# Sheet2.net
KiCad netlist of a schematic drawn in Altium Designer
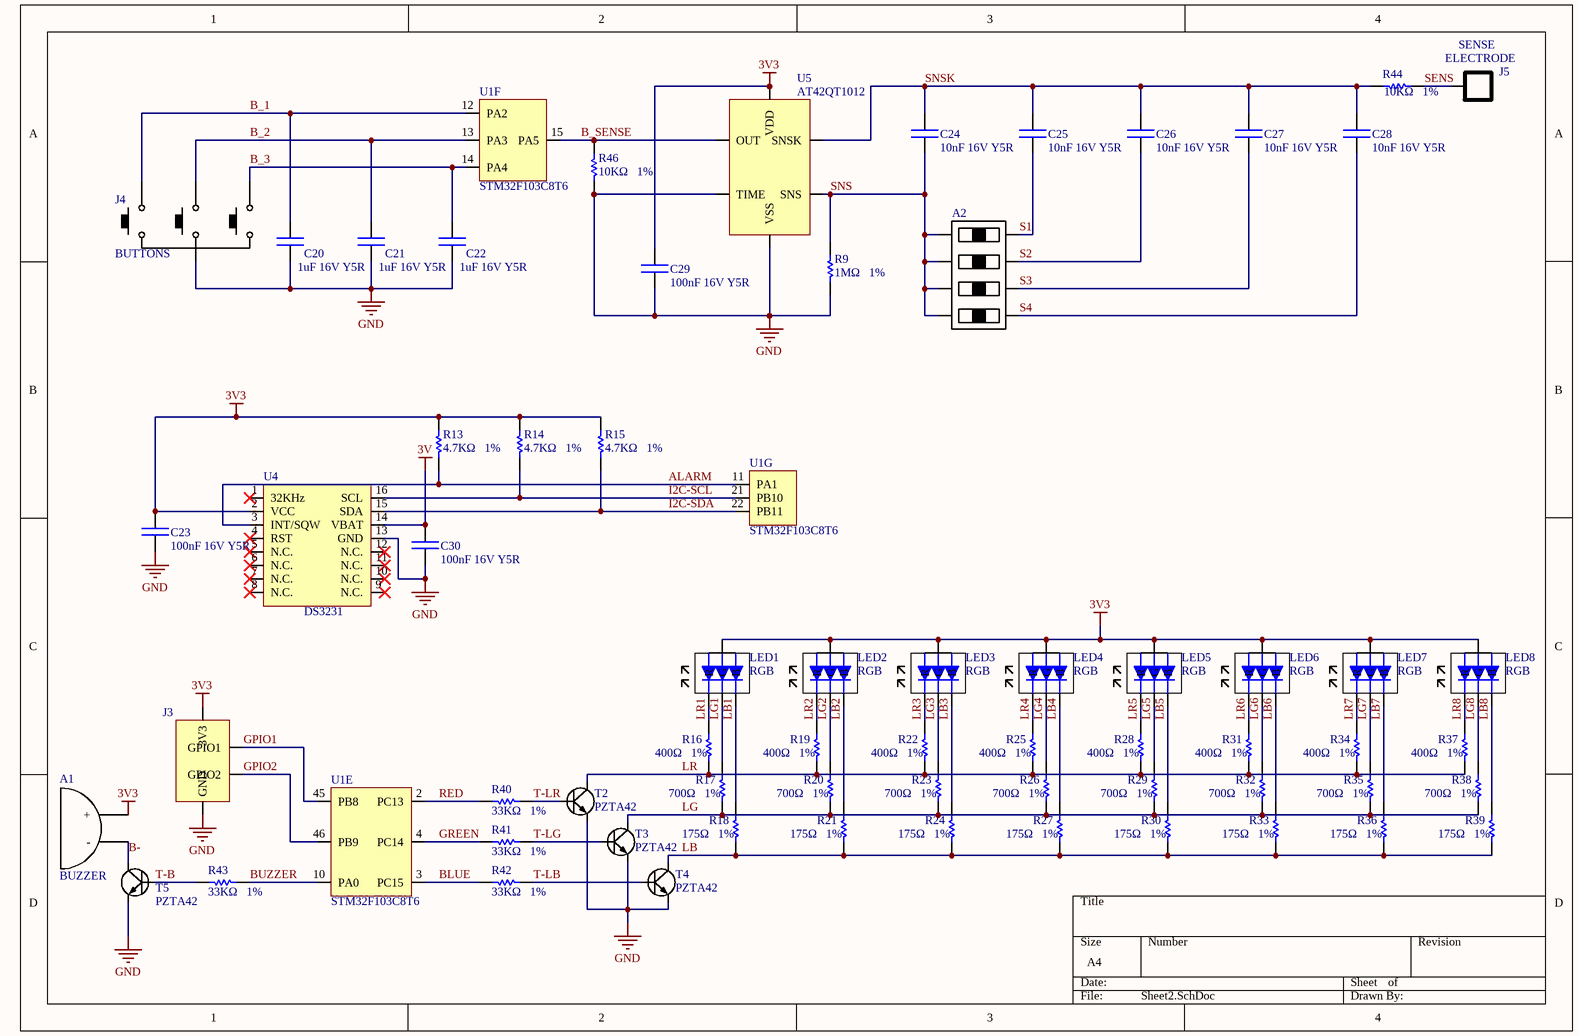
[diagram p0: Sheet2.SchDoc]

(export (version "E")
  (design (tool "Eeschema 10.0.6"))
  (components
    (comp (ref "A1") (value "BUZZER") (footprint "BUZZER") (libsource (lib "Nixielib") (part "BUZZER")))
    (comp (ref "A2")
      (value "DIP-SWITCHx4")
      (footprint "DIP-SWITCH-X4-J-BEND")
      (libsource (lib "Nixielib") (part "DIP-SWITCHx4"))
    )
    (comp (ref "C20") (value "1uF 16V Y5R") (footprint "0603") (libsource (lib "Nixielib") (part "CAP")))
    (comp (ref "C21") (value "1uF 16V Y5R") (footprint "0603") (libsource (lib "Nixielib") (part "CAP")))
    (comp (ref "C22") (value "1uF 16V Y5R") (footprint "0603") (libsource (lib "Nixielib") (part "CAP")))
    (comp (ref "C23") (value "100nF 16V Y5R") (footprint "0603") (libsource (lib "Nixielib") (part "CAP")))
    (comp (ref "C24") (value "10nF 16V Y5R") (footprint "0603") (libsource (lib "Nixielib") (part "CAP")))
    (comp (ref "C25") (value "10nF 16V Y5R") (footprint "0603") (libsource (lib "Nixielib") (part "CAP")))
    (comp (ref "C26") (value "10nF 16V Y5R") (footprint "0603") (libsource (lib "Nixielib") (part "CAP")))
    (comp (ref "C27") (value "10nF 16V Y5R") (footprint "0603") (libsource (lib "Nixielib") (part "CAP")))
    (comp (ref "C28") (value "10nF 16V Y5R") (footprint "0603") (libsource (lib "Nixielib") (part "CAP")))
    (comp (ref "C29") (value "100nF 16V Y5R") (footprint "0603") (libsource (lib "Nixielib") (part "CAP")))
    (comp (ref "C30") (value "100nF 16V Y5R") (footprint "0603") (libsource (lib "Nixielib") (part "CAP")))
    (comp (ref "J3") (value "GPIO") (footprint "PIN-HEADERx4-") (libsource (lib "Nixielib") (part "GPIO")))
    (comp (ref "J4") (value "BUTTONS") (footprint "BORNERAx4") (libsource (lib "Nixielib") (part "BUTTONx3")))
    (comp (ref "J5")
      (value "ELECTRODE")
      (footprint "BORNERAx2")
      (libsource (lib "Nixielib") (part "ELECTRODE"))
    )
    (comp (ref "LED1") (value "RGB") (footprint "1205-RGB") (libsource (lib "Nixielib") (part "RGB")))
    (comp (ref "LED2") (value "RGB") (footprint "1205-RGB") (libsource (lib "Nixielib") (part "RGB")))
    (comp (ref "LED3") (value "RGB") (footprint "1205-RGB") (libsource (lib "Nixielib") (part "RGB")))
    (comp (ref "LED4") (value "RGB") (footprint "1205-RGB") (libsource (lib "Nixielib") (part "RGB")))
    (comp (ref "LED5") (value "RGB") (footprint "1205-RGB") (libsource (lib "Nixielib") (part "RGB")))
    (comp (ref "LED6") (value "RGB") (footprint "1205-RGB") (libsource (lib "Nixielib") (part "RGB")))
    (comp (ref "LED7") (value "RGB") (footprint "1205-RGB") (libsource (lib "Nixielib") (part "RGB")))
    (comp (ref "LED8") (value "RGB") (footprint "1205-RGB") (libsource (lib "Nixielib") (part "RGB")))
    (comp (ref "R9") (value "1MΩ   1%") (footprint "0603") (libsource (lib "Nixielib") (part "RES")))
    (comp (ref "R13") (value "4.7KΩ   1%") (footprint "0603") (libsource (lib "Nixielib") (part "RES")))
    (comp (ref "R14") (value "4.7KΩ   1%") (footprint "0603") (libsource (lib "Nixielib") (part "RES")))
    (comp (ref "R15") (value "4.7KΩ   1%") (footprint "0603") (libsource (lib "Nixielib") (part "RES")))
    (comp (ref "R16") (value "400Ω   1%") (footprint "0603") (libsource (lib "Nixielib") (part "RES")))
    (comp (ref "R17") (value "700Ω   1%") (footprint "0603") (libsource (lib "Nixielib") (part "RES")))
    (comp (ref "R18") (value "175Ω   1%") (footprint "0603") (libsource (lib "Nixielib") (part "RES")))
    (comp (ref "R19") (value "400Ω   1%") (footprint "0603") (libsource (lib "Nixielib") (part "RES")))
    (comp (ref "R20") (value "700Ω   1%") (footprint "0603") (libsource (lib "Nixielib") (part "RES")))
    (comp (ref "R21") (value "175Ω   1%") (footprint "0603") (libsource (lib "Nixielib") (part "RES")))
    (comp (ref "R22") (value "400Ω   1%") (footprint "0603") (libsource (lib "Nixielib") (part "RES")))
    (comp (ref "R23") (value "700Ω   1%") (footprint "0603") (libsource (lib "Nixielib") (part "RES")))
    (comp (ref "R24") (value "175Ω   1%") (footprint "0603") (libsource (lib "Nixielib") (part "RES")))
    (comp (ref "R25") (value "400Ω   1%") (footprint "0603") (libsource (lib "Nixielib") (part "RES")))
    (comp (ref "R26") (value "700Ω   1%") (footprint "0603") (libsource (lib "Nixielib") (part "RES")))
    (comp (ref "R27") (value "175Ω   1%") (footprint "0603") (libsource (lib "Nixielib") (part "RES")))
    (comp (ref "R28") (value "400Ω   1%") (footprint "0603") (libsource (lib "Nixielib") (part "RES")))
    (comp (ref "R29") (value "700Ω   1%") (footprint "0603") (libsource (lib "Nixielib") (part "RES")))
    (comp (ref "R30") (value "175Ω   1%") (footprint "0603") (libsource (lib "Nixielib") (part "RES")))
    (comp (ref "R31") (value "400Ω   1%") (footprint "0603") (libsource (lib "Nixielib") (part "RES")))
    (comp (ref "R32") (value "700Ω   1%") (footprint "0603") (libsource (lib "Nixielib") (part "RES")))
    (comp (ref "R33") (value "175Ω   1%") (footprint "0603") (libsource (lib "Nixielib") (part "RES")))
    (comp (ref "R34") (value "400Ω   1%") (footprint "0603") (libsource (lib "Nixielib") (part "RES")))
    (comp (ref "R35") (value "700Ω   1%") (footprint "0603") (libsource (lib "Nixielib") (part "RES")))
    (comp (ref "R36") (value "175Ω   1%") (footprint "0603") (libsource (lib "Nixielib") (part "RES")))
    (comp (ref "R37") (value "400Ω   1%") (footprint "0603") (libsource (lib "Nixielib") (part "RES")))
    (comp (ref "R38") (value "700Ω   1%") (footprint "0603") (libsource (lib "Nixielib") (part "RES")))
    (comp (ref "R39") (value "175Ω   1%") (footprint "0603") (libsource (lib "Nixielib") (part "RES")))
    (comp (ref "R40") (value "33KΩ   1%") (footprint "0603") (libsource (lib "Nixielib") (part "RES")))
    (comp (ref "R41") (value "33KΩ   1%") (footprint "0603") (libsource (lib "Nixielib") (part "RES")))
    (comp (ref "R42") (value "33KΩ   1%") (footprint "0603") (libsource (lib "Nixielib") (part "RES")))
    (comp (ref "R43") (value "33KΩ   1%") (footprint "0603") (libsource (lib "Nixielib") (part "RES")))
    (comp (ref "R44") (value "10KΩ   1%") (footprint "0603") (libsource (lib "Nixielib") (part "RES")))
    (comp (ref "R46") (value "10KΩ   1%") (footprint "0603") (libsource (lib "Nixielib") (part "RES")))
    (comp (ref "T2") (value "PZTA42") (footprint "SOT-23") (libsource (lib "Nixielib") (part "NPN")))
    (comp (ref "T3") (value "PZTA42") (footprint "SOT-23") (libsource (lib "Nixielib") (part "NPN")))
    (comp (ref "T4") (value "PZTA42") (footprint "SOT-23") (libsource (lib "Nixielib") (part "NPN")))
    (comp (ref "T5") (value "PZTA42") (footprint "SOT-23") (libsource (lib "Nixielib") (part "NPN")))
    (comp (ref "U1")
      (value "STM32F103C8T6")
      (footprint "LQFP48")
      (libsource (lib "Nixielib") (part "STM32F103C8T6"))
    )
    (comp (ref "U4") (value "DS3231") (footprint "SO16W") (libsource (lib "Nixielib") (part "DS3231")))
    (comp (ref "U5")
      (value "AT42QT1012")
      (footprint "SOT-23-6")
      (libsource (lib "Nixielib") (part "AT42QT1012"))
    )
  )
  (nets
    (net (code "1") (name "/ALARM") (class "Default")
      (node (ref "R13") (pin "1") (pinfunction "1_1") (pintype "passive"))
      (node (ref "U1") (pin "11") (pinfunction "PA1_11") (pintype "passive"))
      (node (ref "U4") (pin "3") (pinfunction "INT/SQW_3") (pintype "passive"))
    )
    (net (code "2") (name "/B-") (class "Default")
      (node (ref "A1") (pin "2") (pinfunction "-_2") (pintype "passive"))
      (node (ref "T5") (pin "3") (pinfunction "C_3") (pintype "passive"))
    )
    (net (code "3") (name "/BLUE") (class "Default")
      (node (ref "R42") (pin "1") (pinfunction "1_1") (pintype "passive"))
      (node (ref "U1") (pin "3") (pinfunction "PC15_3") (pintype "passive"))
    )
    (net (code "4") (name "/BUZZER") (class "Default")
      (node (ref "R43") (pin "2") (pinfunction "2_2") (pintype "passive"))
      (node (ref "U1") (pin "10") (pinfunction "PA0_10") (pintype "passive"))
    )
    (net (code "5") (name "/B_1") (class "Default")
      (node (ref "C20") (pin "2") (pinfunction "2_2") (pintype "passive"))
      (node (ref "J4") (pin "1") (pinfunction "1_1") (pintype "passive"))
      (node (ref "U1") (pin "12") (pinfunction "PA2_12") (pintype "passive"))
    )
    (net (code "6") (name "/B_2") (class "Default")
      (node (ref "C21") (pin "2") (pinfunction "2_2") (pintype "passive"))
      (node (ref "J4") (pin "2") (pinfunction "2_2") (pintype "passive"))
      (node (ref "U1") (pin "13") (pinfunction "PA3_13") (pintype "passive"))
    )
    (net (code "7") (name "/B_3") (class "Default")
      (node (ref "C22") (pin "2") (pinfunction "2_2") (pintype "passive"))
      (node (ref "J4") (pin "3") (pinfunction "3_3") (pintype "passive"))
      (node (ref "U1") (pin "14") (pinfunction "PA4_14") (pintype "passive"))
    )
    (net (code "8") (name "/B_SENSE") (class "Default")
      (node (ref "R46") (pin "2") (pinfunction "2_2") (pintype "passive"))
      (node (ref "U1") (pin "15") (pinfunction "PA5_15") (pintype "passive"))
      (node (ref "U5") (pin "1") (pinfunction "OUT_1") (pintype "passive"))
    )
    (net (code "9") (name "/GPIO1") (class "Default")
      (node (ref "J3") (pin "2") (pinfunction "GPIO1_2") (pintype "passive"))
      (node (ref "U1") (pin "45") (pinfunction "PB8_45") (pintype "passive"))
    )
    (net (code "10") (name "/GPIO2") (class "Default")
      (node (ref "J3") (pin "3") (pinfunction "GPIO2_3") (pintype "passive"))
      (node (ref "U1") (pin "46") (pinfunction "PB9_46") (pintype "passive"))
    )
    (net (code "11") (name "/GREEN") (class "Default")
      (node (ref "R41") (pin "1") (pinfunction "1_1") (pintype "passive"))
      (node (ref "U1") (pin "4") (pinfunction "PC14_4") (pintype "passive"))
    )
    (net (code "12") (name "/I2C-SCL") (class "Default")
      (node (ref "R14") (pin "1") (pinfunction "1_1") (pintype "passive"))
      (node (ref "U1") (pin "21") (pinfunction "PB10_21") (pintype "passive"))
      (node (ref "U4") (pin "16") (pinfunction "SCL_16") (pintype "passive"))
    )
    (net (code "13") (name "/I2C-SDA") (class "Default")
      (node (ref "R15") (pin "1") (pinfunction "1_1") (pintype "passive"))
      (node (ref "U1") (pin "22") (pinfunction "PB11_22") (pintype "passive"))
      (node (ref "U4") (pin "15") (pinfunction "SDA_15") (pintype "passive"))
    )
    (net (code "14") (name "/LB") (class "Default")
      (node (ref "R18") (pin "1") (pinfunction "1_1") (pintype "passive"))
      (node (ref "R21") (pin "1") (pinfunction "1_1") (pintype "passive"))
      (node (ref "R24") (pin "1") (pinfunction "1_1") (pintype "passive"))
      (node (ref "R27") (pin "1") (pinfunction "1_1") (pintype "passive"))
      (node (ref "R30") (pin "1") (pinfunction "1_1") (pintype "passive"))
      (node (ref "R33") (pin "1") (pinfunction "1_1") (pintype "passive"))
      (node (ref "R36") (pin "1") (pinfunction "1_1") (pintype "passive"))
      (node (ref "R39") (pin "1") (pinfunction "1_1") (pintype "passive"))
      (node (ref "T4") (pin "3") (pinfunction "C_3") (pintype "passive"))
    )
    (net (code "15") (name "/LB1") (class "Default")
      (node (ref "LED1") (pin "3") (pinfunction "B_3") (pintype "passive"))
      (node (ref "R18") (pin "2") (pinfunction "2_2") (pintype "passive"))
    )
    (net (code "16") (name "/LB2") (class "Default")
      (node (ref "LED2") (pin "3") (pinfunction "B_3") (pintype "passive"))
      (node (ref "R21") (pin "2") (pinfunction "2_2") (pintype "passive"))
    )
    (net (code "17") (name "/LB3") (class "Default")
      (node (ref "LED3") (pin "3") (pinfunction "B_3") (pintype "passive"))
      (node (ref "R24") (pin "2") (pinfunction "2_2") (pintype "passive"))
    )
    (net (code "18") (name "/LB4") (class "Default")
      (node (ref "LED4") (pin "3") (pinfunction "B_3") (pintype "passive"))
      (node (ref "R27") (pin "2") (pinfunction "2_2") (pintype "passive"))
    )
    (net (code "19") (name "/LB5") (class "Default")
      (node (ref "LED5") (pin "3") (pinfunction "B_3") (pintype "passive"))
      (node (ref "R30") (pin "2") (pinfunction "2_2") (pintype "passive"))
    )
    (net (code "20") (name "/LB6") (class "Default")
      (node (ref "LED6") (pin "3") (pinfunction "B_3") (pintype "passive"))
      (node (ref "R33") (pin "2") (pinfunction "2_2") (pintype "passive"))
    )
    (net (code "21") (name "/LB7") (class "Default")
      (node (ref "LED7") (pin "3") (pinfunction "B_3") (pintype "passive"))
      (node (ref "R36") (pin "2") (pinfunction "2_2") (pintype "passive"))
    )
    (net (code "22") (name "/LB8") (class "Default")
      (node (ref "LED8") (pin "3") (pinfunction "B_3") (pintype "passive"))
      (node (ref "R39") (pin "2") (pinfunction "2_2") (pintype "passive"))
    )
    (net (code "23") (name "/LG") (class "Default")
      (node (ref "R17") (pin "1") (pinfunction "1_1") (pintype "passive"))
      (node (ref "R20") (pin "1") (pinfunction "1_1") (pintype "passive"))
      (node (ref "R23") (pin "1") (pinfunction "1_1") (pintype "passive"))
      (node (ref "R26") (pin "1") (pinfunction "1_1") (pintype "passive"))
      (node (ref "R29") (pin "1") (pinfunction "1_1") (pintype "passive"))
      (node (ref "R32") (pin "1") (pinfunction "1_1") (pintype "passive"))
      (node (ref "R35") (pin "1") (pinfunction "1_1") (pintype "passive"))
      (node (ref "R38") (pin "1") (pinfunction "1_1") (pintype "passive"))
      (node (ref "T3") (pin "3") (pinfunction "C_3") (pintype "passive"))
    )
    (net (code "24") (name "/LG1") (class "Default")
      (node (ref "LED1") (pin "4") (pinfunction "G_4") (pintype "passive"))
      (node (ref "R17") (pin "2") (pinfunction "2_2") (pintype "passive"))
    )
    (net (code "25") (name "/LG2") (class "Default")
      (node (ref "LED2") (pin "4") (pinfunction "G_4") (pintype "passive"))
      (node (ref "R20") (pin "2") (pinfunction "2_2") (pintype "passive"))
    )
    (net (code "26") (name "/LG3") (class "Default")
      (node (ref "LED3") (pin "4") (pinfunction "G_4") (pintype "passive"))
      (node (ref "R23") (pin "2") (pinfunction "2_2") (pintype "passive"))
    )
    (net (code "27") (name "/LG4") (class "Default")
      (node (ref "LED4") (pin "4") (pinfunction "G_4") (pintype "passive"))
      (node (ref "R26") (pin "2") (pinfunction "2_2") (pintype "passive"))
    )
    (net (code "28") (name "/LG5") (class "Default")
      (node (ref "LED5") (pin "4") (pinfunction "G_4") (pintype "passive"))
      (node (ref "R29") (pin "2") (pinfunction "2_2") (pintype "passive"))
    )
    (net (code "29") (name "/LG6") (class "Default")
      (node (ref "LED6") (pin "4") (pinfunction "G_4") (pintype "passive"))
      (node (ref "R32") (pin "2") (pinfunction "2_2") (pintype "passive"))
    )
    (net (code "30") (name "/LG7") (class "Default")
      (node (ref "LED7") (pin "4") (pinfunction "G_4") (pintype "passive"))
      (node (ref "R35") (pin "2") (pinfunction "2_2") (pintype "passive"))
    )
    (net (code "31") (name "/LG8") (class "Default")
      (node (ref "LED8") (pin "4") (pinfunction "G_4") (pintype "passive"))
      (node (ref "R38") (pin "2") (pinfunction "2_2") (pintype "passive"))
    )
    (net (code "32") (name "/LR") (class "Default")
      (node (ref "R16") (pin "1") (pinfunction "1_1") (pintype "passive"))
      (node (ref "R19") (pin "1") (pinfunction "1_1") (pintype "passive"))
      (node (ref "R22") (pin "1") (pinfunction "1_1") (pintype "passive"))
      (node (ref "R25") (pin "1") (pinfunction "1_1") (pintype "passive"))
      (node (ref "R28") (pin "1") (pinfunction "1_1") (pintype "passive"))
      (node (ref "R31") (pin "1") (pinfunction "1_1") (pintype "passive"))
      (node (ref "R34") (pin "1") (pinfunction "1_1") (pintype "passive"))
      (node (ref "R37") (pin "1") (pinfunction "1_1") (pintype "passive"))
      (node (ref "T2") (pin "3") (pinfunction "C_3") (pintype "passive"))
    )
    (net (code "33") (name "/LR1") (class "Default")
      (node (ref "LED1") (pin "1") (pinfunction "R_1") (pintype "passive"))
      (node (ref "R16") (pin "2") (pinfunction "2_2") (pintype "passive"))
    )
    (net (code "34") (name "/LR2") (class "Default")
      (node (ref "LED2") (pin "1") (pinfunction "R_1") (pintype "passive"))
      (node (ref "R19") (pin "2") (pinfunction "2_2") (pintype "passive"))
    )
    (net (code "35") (name "/LR3") (class "Default")
      (node (ref "LED3") (pin "1") (pinfunction "R_1") (pintype "passive"))
      (node (ref "R22") (pin "2") (pinfunction "2_2") (pintype "passive"))
    )
    (net (code "36") (name "/LR4") (class "Default")
      (node (ref "LED4") (pin "1") (pinfunction "R_1") (pintype "passive"))
      (node (ref "R25") (pin "2") (pinfunction "2_2") (pintype "passive"))
    )
    (net (code "37") (name "/LR5") (class "Default")
      (node (ref "LED5") (pin "1") (pinfunction "R_1") (pintype "passive"))
      (node (ref "R28") (pin "2") (pinfunction "2_2") (pintype "passive"))
    )
    (net (code "38") (name "/LR6") (class "Default")
      (node (ref "LED6") (pin "1") (pinfunction "R_1") (pintype "passive"))
      (node (ref "R31") (pin "2") (pinfunction "2_2") (pintype "passive"))
    )
    (net (code "39") (name "/LR7") (class "Default")
      (node (ref "LED7") (pin "1") (pinfunction "R_1") (pintype "passive"))
      (node (ref "R34") (pin "2") (pinfunction "2_2") (pintype "passive"))
    )
    (net (code "40") (name "/LR8") (class "Default")
      (node (ref "LED8") (pin "1") (pinfunction "R_1") (pintype "passive"))
      (node (ref "R37") (pin "2") (pinfunction "2_2") (pintype "passive"))
    )
    (net (code "41") (name "/RED") (class "Default")
      (node (ref "R40") (pin "1") (pinfunction "1_1") (pintype "passive"))
      (node (ref "U1") (pin "2") (pinfunction "PC13_2") (pintype "passive"))
    )
    (net (code "42") (name "/S1") (class "Default")
      (node (ref "A2") (pin "8") (pinfunction "8_8") (pintype "passive"))
      (node (ref "C25") (pin "2") (pinfunction "2_2") (pintype "passive"))
    )
    (net (code "43") (name "/S2") (class "Default")
      (node (ref "A2") (pin "7") (pinfunction "7_7") (pintype "passive"))
      (node (ref "C26") (pin "2") (pinfunction "2_2") (pintype "passive"))
    )
    (net (code "44") (name "/S3") (class "Default")
      (node (ref "A2") (pin "6") (pinfunction "6_6") (pintype "passive"))
      (node (ref "C27") (pin "2") (pinfunction "2_2") (pintype "passive"))
    )
    (net (code "45") (name "/S4") (class "Default")
      (node (ref "A2") (pin "5") (pinfunction "5_5") (pintype "passive"))
      (node (ref "C28") (pin "2") (pinfunction "2_2") (pintype "passive"))
    )
    (net (code "46") (name "/SENS") (class "Default")
      (node (ref "J5") (pin "1") (pinfunction "1_1") (pintype "passive"))
      (node (ref "R44") (pin "1") (pinfunction "1_1") (pintype "passive"))
    )
    (net (code "47") (name "/SNS") (class "Default")
      (node (ref "A2") (pin "1") (pinfunction "1_1") (pintype "passive"))
      (node (ref "A2") (pin "2") (pinfunction "2_2") (pintype "passive"))
      (node (ref "A2") (pin "3") (pinfunction "3_3") (pintype "passive"))
      (node (ref "A2") (pin "4") (pinfunction "4_4") (pintype "passive"))
      (node (ref "C24") (pin "2") (pinfunction "2_2") (pintype "passive"))
      (node (ref "R9") (pin "1") (pinfunction "1_1") (pintype "passive"))
      (node (ref "U5") (pin "4") (pinfunction "SNS_4") (pintype "passive"))
    )
    (net (code "48") (name "/SNSK") (class "Default")
      (node (ref "C24") (pin "1") (pinfunction "1_1") (pintype "passive"))
      (node (ref "C25") (pin "1") (pinfunction "1_1") (pintype "passive"))
      (node (ref "C26") (pin "1") (pinfunction "1_1") (pintype "passive"))
      (node (ref "C27") (pin "1") (pinfunction "1_1") (pintype "passive"))
      (node (ref "C28") (pin "1") (pinfunction "1_1") (pintype "passive"))
      (node (ref "R44") (pin "2") (pinfunction "2_2") (pintype "passive"))
      (node (ref "U5") (pin "3") (pinfunction "SNSK_3") (pintype "passive"))
    )
    (net (code "49") (name "/T-B") (class "Default")
      (node (ref "R43") (pin "1") (pinfunction "1_1") (pintype "passive"))
      (node (ref "T5") (pin "1") (pinfunction "B_1") (pintype "passive"))
    )
    (net (code "50") (name "/T-LB") (class "Default")
      (node (ref "R42") (pin "2") (pinfunction "2_2") (pintype "passive"))
      (node (ref "T4") (pin "1") (pinfunction "B_1") (pintype "passive"))
    )
    (net (code "51") (name "/T-LG") (class "Default")
      (node (ref "R41") (pin "2") (pinfunction "2_2") (pintype "passive"))
      (node (ref "T3") (pin "1") (pinfunction "B_1") (pintype "passive"))
    )
    (net (code "52") (name "/T-LR") (class "Default")
      (node (ref "R40") (pin "2") (pinfunction "2_2") (pintype "passive"))
      (node (ref "T2") (pin "1") (pinfunction "B_1") (pintype "passive"))
    )
    (net (code "53") (name "3V") (class "Default")
      (node (ref "C30") (pin "2") (pinfunction "2_2") (pintype "passive"))
      (node (ref "U4") (pin "14") (pinfunction "VBAT_14") (pintype "passive"))
    )
    (net (code "54") (name "3V3") (class "Default")
      (node (ref "A1") (pin "1") (pinfunction "+_1") (pintype "passive"))
      (node (ref "C23") (pin "2") (pinfunction "2_2") (pintype "passive"))
      (node (ref "C29") (pin "1") (pinfunction "1_1") (pintype "passive"))
      (node (ref "J3") (pin "1") (pinfunction "3V3_1") (pintype "passive"))
      (node (ref "LED1") (pin "2") (pinfunction "A_2") (pintype "passive"))
      (node (ref "LED2") (pin "2") (pinfunction "A_2") (pintype "passive"))
      (node (ref "LED3") (pin "2") (pinfunction "A_2") (pintype "passive"))
      (node (ref "LED4") (pin "2") (pinfunction "A_2") (pintype "passive"))
      (node (ref "LED5") (pin "2") (pinfunction "A_2") (pintype "passive"))
      (node (ref "LED6") (pin "2") (pinfunction "A_2") (pintype "passive"))
      (node (ref "LED7") (pin "2") (pinfunction "A_2") (pintype "passive"))
      (node (ref "LED8") (pin "2") (pinfunction "A_2") (pintype "passive"))
      (node (ref "R13") (pin "2") (pinfunction "2_2") (pintype "passive"))
      (node (ref "R14") (pin "2") (pinfunction "2_2") (pintype "passive"))
      (node (ref "R15") (pin "2") (pinfunction "2_2") (pintype "passive"))
      (node (ref "U4") (pin "2") (pinfunction "VCC_2") (pintype "passive"))
      (node (ref "U5") (pin "5") (pinfunction "VDD_5") (pintype "passive"))
    )
    (net (code "55") (name "GND") (class "Default")
      (node (ref "C20") (pin "1") (pinfunction "1_1") (pintype "passive"))
      (node (ref "C21") (pin "1") (pinfunction "1_1") (pintype "passive"))
      (node (ref "C22") (pin "1") (pinfunction "1_1") (pintype "passive"))
      (node (ref "C23") (pin "1") (pinfunction "1_1") (pintype "passive"))
      (node (ref "C29") (pin "2") (pinfunction "2_2") (pintype "passive"))
      (node (ref "C30") (pin "1") (pinfunction "1_1") (pintype "passive"))
      (node (ref "J3") (pin "4") (pinfunction "GND_4") (pintype "passive"))
      (node (ref "J4") (pin "4") (pinfunction "4_4") (pintype "passive"))
      (node (ref "R46") (pin "1") (pinfunction "1_1") (pintype "passive"))
      (node (ref "R9") (pin "2") (pinfunction "2_2") (pintype "passive"))
      (node (ref "T2") (pin "2") (pinfunction "E_2") (pintype "passive"))
      (node (ref "T3") (pin "2") (pinfunction "E_2") (pintype "passive"))
      (node (ref "T4") (pin "2") (pinfunction "E_2") (pintype "passive"))
      (node (ref "T5") (pin "2") (pinfunction "E_2") (pintype "passive"))
      (node (ref "U4") (pin "13") (pinfunction "GND_13") (pintype "passive"))
      (node (ref "U5") (pin "2") (pinfunction "VSS_2") (pintype "passive"))
      (node (ref "U5") (pin "6") (pinfunction "TIME_6") (pintype "passive"))
    )
    (net (code "56") (name "unconnected-(U4-32KHz-Pad1)") (class "Default")
      (node (ref "U4") (pin "1") (pinfunction "32KHz_1") (pintype "passive+no_connect"))
    )
    (net (code "57") (name "unconnected-(U4-N.C.-Pad5)") (class "Default")
      (node (ref "U4") (pin "5") (pinfunction "N.C._5") (pintype "passive+no_connect"))
    )
    (net (code "58") (name "unconnected-(U4-N.C.-Pad6)") (class "Default")
      (node (ref "U4") (pin "6") (pinfunction "N.C._6") (pintype "passive+no_connect"))
    )
    (net (code "59") (name "unconnected-(U4-N.C.-Pad7)") (class "Default")
      (node (ref "U4") (pin "7") (pinfunction "N.C._7") (pintype "passive+no_connect"))
    )
    (net (code "60") (name "unconnected-(U4-N.C.-Pad8)") (class "Default")
      (node (ref "U4") (pin "8") (pinfunction "N.C._8") (pintype "passive+no_connect"))
    )
    (net (code "61") (name "unconnected-(U4-N.C.-Pad9)") (class "Default")
      (node (ref "U4") (pin "9") (pinfunction "N.C._9") (pintype "passive+no_connect"))
    )
    (net (code "62") (name "unconnected-(U4-N.C.-Pad10)") (class "Default")
      (node (ref "U4") (pin "10") (pinfunction "N.C._10") (pintype "passive+no_connect"))
    )
    (net (code "63") (name "unconnected-(U4-N.C.-Pad11)") (class "Default")
      (node (ref "U4") (pin "11") (pinfunction "N.C._11") (pintype "passive+no_connect"))
    )
    (net (code "64") (name "unconnected-(U4-N.C.-Pad12)") (class "Default")
      (node (ref "U4") (pin "12") (pinfunction "N.C._12") (pintype "passive+no_connect"))
    )
    (net (code "65") (name "unconnected-(U4-RST-Pad4)") (class "Default")
      (node (ref "U4") (pin "4") (pinfunction "RST_4") (pintype "passive+no_connect"))
    )
  )
)
